# IRIS-FE-01-B-LEDs.net
KiCad netlist of a schematic drawn in Altium Designer
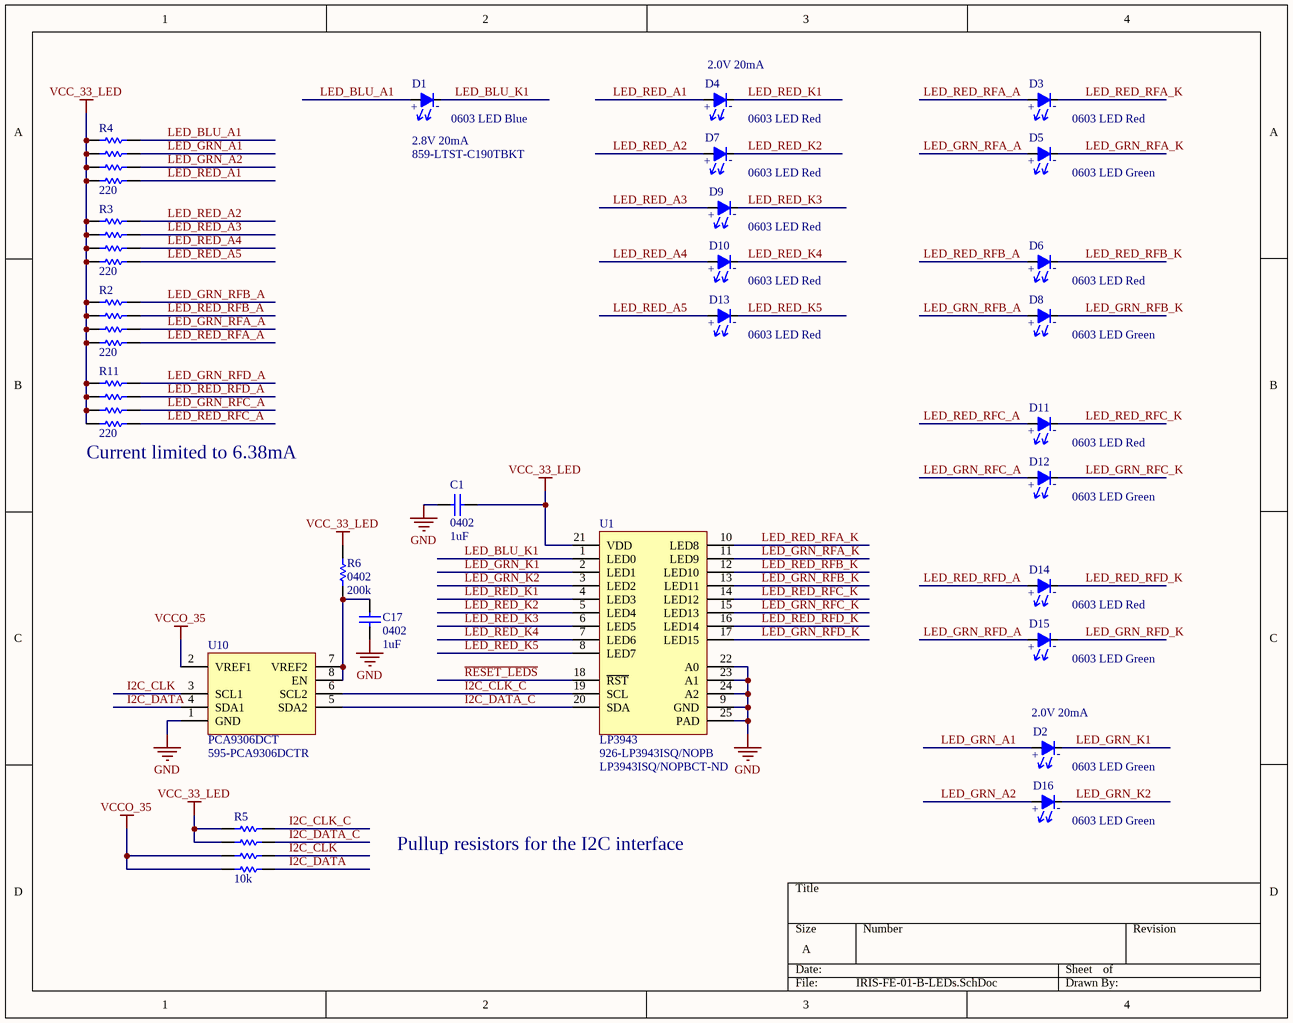
[diagram p0: IRIS-FE-01-B-LEDs.SchDoc]

(export (version "E")
  (design (tool "Eeschema 10.0.6"))
  (components
    (comp (ref "C1")
      (value "0402")
      (footprint "0402_SMT_CAP")
      (description "0402 SMT Capacitor")
      (fields (field (name "ALTIUM_VALUE") "1uF"))
      (libsource (lib "RNG_Parts") (part "Cap_0402"))
    )
    (comp (ref "C17")
      (value "0402")
      (footprint "0402_SMT_CAP")
      (description "0402 SMT Capacitor")
      (fields (field (name "ALTIUM_VALUE") "1uF"))
      (libsource (lib "RNG_Parts") (part "Cap_0402"))
    )
    (comp (ref "D1")
      (value "0603 LED Blue")
      (footprint "0603_SMT_LED_Blue")
      (description "0603 LED with Polar Markings")
      (fields
        (field (name "ALTIUM_VALUE") "2.8V 20mA")
        (field (name "SUPPLIER PART NUMBER 1") "859-LTST-C190TBKT")
      )
      (libsource (lib "Skylark_Master") (part "LED_0603_BLUE"))
    )
    (comp (ref "D2")
      (value "0603 LED Green")
      (footprint "0603_SMT_LED_Green")
      (description "0603 LED with Polar Markings")
      (fields (field (name "ALTIUM_VALUE") "2.0V 20mA"))
      (libsource (lib "Skylark_Master") (part "LED_0603_GREEN"))
    )
    (comp (ref "D3")
      (value "0603 LED Red")
      (footprint "0603_SMT_LED_Red")
      (description "0603 LED with Polar Markings")
      (libsource (lib "Skylark_Master") (part "LED_0603_RED"))
    )
    (comp (ref "D4")
      (value "0603 LED Red")
      (footprint "0603_SMT_LED_Red")
      (description "0603 LED with Polar Markings")
      (fields (field (name "ALTIUM_VALUE") "2.0V 20mA"))
      (libsource (lib "Skylark_Master") (part "LED_0603_RED"))
    )
    (comp (ref "D5")
      (value "0603 LED Green")
      (footprint "0603_SMT_LED_Green")
      (description "0603 LED with Polar Markings")
      (libsource (lib "Skylark_Master") (part "LED_0603_GREEN"))
    )
    (comp (ref "D6")
      (value "0603 LED Red")
      (footprint "0603_SMT_LED_Red")
      (description "0603 LED with Polar Markings")
      (libsource (lib "Skylark_Master") (part "LED_0603_RED"))
    )
    (comp (ref "D7")
      (value "0603 LED Red")
      (footprint "0603_SMT_LED_Red")
      (description "0603 LED with Polar Markings")
      (libsource (lib "Skylark_Master") (part "LED_0603_RED"))
    )
    (comp (ref "D8")
      (value "0603 LED Green")
      (footprint "0603_SMT_LED_Green")
      (description "0603 LED with Polar Markings")
      (libsource (lib "Skylark_Master") (part "LED_0603_GREEN"))
    )
    (comp (ref "D9")
      (value "0603 LED Red")
      (footprint "0603_SMT_LED_Red")
      (description "0603 LED with Polar Markings")
      (libsource (lib "Skylark_Master") (part "LED_0603_RED"))
    )
    (comp (ref "D10")
      (value "0603 LED Red")
      (footprint "0603_SMT_LED_Red")
      (description "0603 LED with Polar Markings")
      (libsource (lib "Skylark_Master") (part "LED_0603_RED"))
    )
    (comp (ref "D11")
      (value "0603 LED Red")
      (footprint "0603_SMT_LED_Red")
      (description "0603 LED with Polar Markings")
      (libsource (lib "Skylark_Master") (part "LED_0603_RED"))
    )
    (comp (ref "D12")
      (value "0603 LED Green")
      (footprint "0603_SMT_LED_Green")
      (description "0603 LED with Polar Markings")
      (libsource (lib "Skylark_Master") (part "LED_0603_GREEN"))
    )
    (comp (ref "D13")
      (value "0603 LED Red")
      (footprint "0603_SMT_LED_Red")
      (description "0603 LED with Polar Markings")
      (libsource (lib "Skylark_Master") (part "LED_0603_RED"))
    )
    (comp (ref "D14")
      (value "0603 LED Red")
      (footprint "0603_SMT_LED_Red")
      (description "0603 LED with Polar Markings")
      (libsource (lib "Skylark_Master") (part "LED_0603_RED"))
    )
    (comp (ref "D15")
      (value "0603 LED Green")
      (footprint "0603_SMT_LED_Green")
      (description "0603 LED with Polar Markings")
      (libsource (lib "Skylark_Master") (part "LED_0603_GREEN"))
    )
    (comp (ref "D16")
      (value "0603 LED Green")
      (footprint "0603_SMT_LED_Green")
      (description "0603 LED with Polar Markings")
      (libsource (lib "Skylark_Master") (part "LED_0603_GREEN"))
    )
    (comp (ref "R2")
      (value "220")
      (footprint "EXB28V")
      (description "0402 SMT Resistor Array")
      (fields (field (name "Comment") "0402 Array"))
      (libsource (lib "Skylark_Master") (part "Res_0402_4xArray"))
    )
    (comp (ref "R3")
      (value "220")
      (footprint "EXB28V")
      (description "0402 SMT Resistor Array")
      (fields (field (name "Comment") "0402 Array"))
      (libsource (lib "Skylark_Master") (part "Res_0402_4xArray"))
    )
    (comp (ref "R4")
      (value "220")
      (footprint "EXB28V")
      (description "0402 SMT Resistor Array")
      (fields (field (name "Comment") "0402 Array"))
      (libsource (lib "Skylark_Master") (part "Res_0402_4xArray"))
    )
    (comp (ref "R5")
      (value "10k")
      (footprint "EXB28V")
      (description "0402 SMT Resistor Array")
      (fields (field (name "Comment") "0402 Array"))
      (libsource (lib "Skylark_Master") (part "Res_0402_4xArray"))
    )
    (comp (ref "R6")
      (value "0402")
      (footprint "0402_SMT_RES")
      (description "0402 SMT Resistor")
      (fields (field (name "ALTIUM_VALUE") "200k"))
      (libsource (lib "Skylark_Master") (part "Res_0402"))
    )
    (comp (ref "R11")
      (value "220")
      (footprint "EXB28V")
      (description "0402 SMT Resistor Array")
      (fields (field (name "Comment") "0402 Array"))
      (libsource (lib "Skylark_Master") (part "Res_0402_4xArray"))
    )
    (comp (ref "U1")
      (value "LP3943")
      (footprint "TI-QFN127P600-8N")
      (description "TI 16-LED Fun Light Driver with I2C")
      (fields
        (field (name "SUPPLIER PART NUMBER 1") "926-LP3943ISQ/NOPB")
        (field (name "SUPPLIER PART NUMBER 2") "LP3943ISQ/NOPBCT-ND")
      )
      (libsource (lib "Skylark_Master") (part "LP3943"))
    )
    (comp (ref "U10")
      (value "PCA9306DCT")
      (footprint "TI-SOP127P600-8N")
      (description "TI I2C Bidirectional Voltage Translator")
      (fields (field (name "SUPPLIER PART NUMBER 1") "595-PCA9306DCTR"))
      (libsource (lib "Skylark_Master") (part "PCA9306DCT"))
    )
  )
  (nets
    (net (code "1") (name "/I2C_CLK") (class "Default")
      (node (ref "R5") (pin "2") (pinfunction "2_2") (pintype "passive"))
      (node (ref "U10") (pin "3") (pinfunction "SCL1_3") (pintype "passive"))
    )
    (net (code "2") (name "/I2C_CLK_C") (class "Default")
      (node (ref "R5") (pin "4") (pinfunction "4_4") (pintype "passive"))
      (node (ref "U1") (pin "19") (pinfunction "SCL_19") (pintype "passive"))
      (node (ref "U10") (pin "6") (pinfunction "SCL2_6") (pintype "passive"))
    )
    (net (code "3") (name "/I2C_DATA") (class "Default")
      (node (ref "R5") (pin "1") (pinfunction "1_1") (pintype "passive"))
      (node (ref "U10") (pin "4") (pinfunction "SDA1_4") (pintype "passive"))
    )
    (net (code "4") (name "/I2C_DATA_C") (class "Default")
      (node (ref "R5") (pin "3") (pinfunction "3_3") (pintype "passive"))
      (node (ref "U1") (pin "20") (pinfunction "SDA_20") (pintype "passive"))
      (node (ref "U10") (pin "5") (pinfunction "SDA2_5") (pintype "passive"))
    )
    (net (code "5") (name "/LED_BLU_A1") (class "Default")
      (node (ref "D1") (pin "1") (pinfunction "P_1") (pintype "passive"))
      (node (ref "R4") (pin "8") (pinfunction "8_8") (pintype "passive"))
    )
    (net (code "6") (name "/LED_BLU_K1") (class "Default")
      (node (ref "D1") (pin "2") (pinfunction "N_2") (pintype "passive"))
      (node (ref "U1") (pin "1") (pinfunction "LED0_1") (pintype "passive"))
    )
    (net (code "7") (name "/LED_GRN_A1") (class "Default")
      (node (ref "D2") (pin "1") (pinfunction "P_1") (pintype "passive"))
      (node (ref "R4") (pin "7") (pinfunction "7_7") (pintype "passive"))
    )
    (net (code "8") (name "/LED_GRN_A2") (class "Default")
      (node (ref "D16") (pin "1") (pinfunction "P_1") (pintype "passive"))
      (node (ref "R4") (pin "6") (pinfunction "6_6") (pintype "passive"))
    )
    (net (code "9") (name "/LED_GRN_K1") (class "Default")
      (node (ref "D2") (pin "2") (pinfunction "N_2") (pintype "passive"))
      (node (ref "U1") (pin "2") (pinfunction "LED1_2") (pintype "passive"))
    )
    (net (code "10") (name "/LED_GRN_K2") (class "Default")
      (node (ref "D16") (pin "2") (pinfunction "N_2") (pintype "passive"))
      (node (ref "U1") (pin "3") (pinfunction "LED2_3") (pintype "passive"))
    )
    (net (code "11") (name "/LED_GRN_RFA_A") (class "Default")
      (node (ref "D5") (pin "1") (pinfunction "P_1") (pintype "passive"))
      (node (ref "R2") (pin "6") (pinfunction "6_6") (pintype "passive"))
    )
    (net (code "12") (name "/LED_GRN_RFA_K") (class "Default")
      (node (ref "D5") (pin "2") (pinfunction "N_2") (pintype "passive"))
      (node (ref "U1") (pin "11") (pinfunction "LED9_11") (pintype "passive"))
    )
    (net (code "13") (name "/LED_GRN_RFB_A") (class "Default")
      (node (ref "D8") (pin "1") (pinfunction "P_1") (pintype "passive"))
      (node (ref "R2") (pin "8") (pinfunction "8_8") (pintype "passive"))
    )
    (net (code "14") (name "/LED_GRN_RFB_K") (class "Default")
      (node (ref "D8") (pin "2") (pinfunction "N_2") (pintype "passive"))
      (node (ref "U1") (pin "13") (pinfunction "LED11_13") (pintype "passive"))
    )
    (net (code "15") (name "/LED_GRN_RFC_A") (class "Default")
      (node (ref "D12") (pin "1") (pinfunction "P_1") (pintype "passive"))
      (node (ref "R11") (pin "6") (pinfunction "6_6") (pintype "passive"))
    )
    (net (code "16") (name "/LED_GRN_RFC_K") (class "Default")
      (node (ref "D12") (pin "2") (pinfunction "N_2") (pintype "passive"))
      (node (ref "U1") (pin "15") (pinfunction "LED13_15") (pintype "passive"))
    )
    (net (code "17") (name "/LED_GRN_RFD_A") (class "Default")
      (node (ref "D15") (pin "1") (pinfunction "P_1") (pintype "passive"))
      (node (ref "R11") (pin "8") (pinfunction "8_8") (pintype "passive"))
    )
    (net (code "18") (name "/LED_GRN_RFD_K") (class "Default")
      (node (ref "D15") (pin "2") (pinfunction "N_2") (pintype "passive"))
      (node (ref "U1") (pin "17") (pinfunction "LED15_17") (pintype "passive"))
    )
    (net (code "19") (name "/LED_RED_A1") (class "Default")
      (node (ref "D4") (pin "1") (pinfunction "P_1") (pintype "passive"))
      (node (ref "R4") (pin "5") (pinfunction "5_5") (pintype "passive"))
    )
    (net (code "20") (name "/LED_RED_A2") (class "Default")
      (node (ref "D7") (pin "1") (pinfunction "P_1") (pintype "passive"))
      (node (ref "R3") (pin "8") (pinfunction "8_8") (pintype "passive"))
    )
    (net (code "21") (name "/LED_RED_A3") (class "Default")
      (node (ref "D9") (pin "1") (pinfunction "P_1") (pintype "passive"))
      (node (ref "R3") (pin "7") (pinfunction "7_7") (pintype "passive"))
    )
    (net (code "22") (name "/LED_RED_A4") (class "Default")
      (node (ref "D10") (pin "1") (pinfunction "P_1") (pintype "passive"))
      (node (ref "R3") (pin "6") (pinfunction "6_6") (pintype "passive"))
    )
    (net (code "23") (name "/LED_RED_A5") (class "Default")
      (node (ref "D13") (pin "1") (pinfunction "P_1") (pintype "passive"))
      (node (ref "R3") (pin "5") (pinfunction "5_5") (pintype "passive"))
    )
    (net (code "24") (name "/LED_RED_K1") (class "Default")
      (node (ref "D4") (pin "2") (pinfunction "N_2") (pintype "passive"))
      (node (ref "U1") (pin "4") (pinfunction "LED3_4") (pintype "passive"))
    )
    (net (code "25") (name "/LED_RED_K2") (class "Default")
      (node (ref "D7") (pin "2") (pinfunction "N_2") (pintype "passive"))
      (node (ref "U1") (pin "5") (pinfunction "LED4_5") (pintype "passive"))
    )
    (net (code "26") (name "/LED_RED_K3") (class "Default")
      (node (ref "D9") (pin "2") (pinfunction "N_2") (pintype "passive"))
      (node (ref "U1") (pin "6") (pinfunction "LED5_6") (pintype "passive"))
    )
    (net (code "27") (name "/LED_RED_K4") (class "Default")
      (node (ref "D10") (pin "2") (pinfunction "N_2") (pintype "passive"))
      (node (ref "U1") (pin "7") (pinfunction "LED6_7") (pintype "passive"))
    )
    (net (code "28") (name "/LED_RED_K5") (class "Default")
      (node (ref "D13") (pin "2") (pinfunction "N_2") (pintype "passive"))
      (node (ref "U1") (pin "8") (pinfunction "LED7_8") (pintype "passive"))
    )
    (net (code "29") (name "/LED_RED_RFA_A") (class "Default")
      (node (ref "D3") (pin "1") (pinfunction "P_1") (pintype "passive"))
      (node (ref "R2") (pin "5") (pinfunction "5_5") (pintype "passive"))
    )
    (net (code "30") (name "/LED_RED_RFA_K") (class "Default")
      (node (ref "D3") (pin "2") (pinfunction "N_2") (pintype "passive"))
      (node (ref "U1") (pin "10") (pinfunction "LED8_10") (pintype "passive"))
    )
    (net (code "31") (name "/LED_RED_RFB_A") (class "Default")
      (node (ref "D6") (pin "1") (pinfunction "P_1") (pintype "passive"))
      (node (ref "R2") (pin "7") (pinfunction "7_7") (pintype "passive"))
    )
    (net (code "32") (name "/LED_RED_RFB_K") (class "Default")
      (node (ref "D6") (pin "2") (pinfunction "N_2") (pintype "passive"))
      (node (ref "U1") (pin "12") (pinfunction "LED10_12") (pintype "passive"))
    )
    (net (code "33") (name "/LED_RED_RFC_A") (class "Default")
      (node (ref "D11") (pin "1") (pinfunction "P_1") (pintype "passive"))
      (node (ref "R11") (pin "5") (pinfunction "5_5") (pintype "passive"))
    )
    (net (code "34") (name "/LED_RED_RFC_K") (class "Default")
      (node (ref "D11") (pin "2") (pinfunction "N_2") (pintype "passive"))
      (node (ref "U1") (pin "14") (pinfunction "LED12_14") (pintype "passive"))
    )
    (net (code "35") (name "/LED_RED_RFD_A") (class "Default")
      (node (ref "D14") (pin "1") (pinfunction "P_1") (pintype "passive"))
      (node (ref "R11") (pin "7") (pinfunction "7_7") (pintype "passive"))
    )
    (net (code "36") (name "/LED_RED_RFD_K") (class "Default")
      (node (ref "D14") (pin "2") (pinfunction "N_2") (pintype "passive"))
      (node (ref "U1") (pin "16") (pinfunction "LED14_16") (pintype "passive"))
    )
    (net (code "37") (name "/RESET_LEDS") (class "Default")
      (node (ref "U1") (pin "18") (pinfunction "RST_18") (pintype "passive"))
    )
    (net (code "38") (name "GND") (class "Default")
      (node (ref "C1") (pin "2") (pinfunction "2_2") (pintype "passive"))
      (node (ref "C17") (pin "1") (pinfunction "1_1") (pintype "passive"))
      (node (ref "U1") (pin "22") (pinfunction "A0_22") (pintype "passive"))
      (node (ref "U1") (pin "23") (pinfunction "A1_23") (pintype "passive"))
      (node (ref "U1") (pin "24") (pinfunction "A2_24") (pintype "passive"))
      (node (ref "U1") (pin "25") (pinfunction "PAD_25") (pintype "passive"))
      (node (ref "U1") (pin "9") (pinfunction "GND_9") (pintype "passive"))
      (node (ref "U10") (pin "1") (pinfunction "GND_1") (pintype "passive"))
    )
    (net (code "39") (name "Net-(U10-EN)") (class "Default")
      (node (ref "C17") (pin "2") (pinfunction "2_2") (pintype "passive"))
      (node (ref "R6") (pin "1") (pinfunction "1_1") (pintype "passive"))
      (node (ref "U10") (pin "7") (pinfunction "VREF2_7") (pintype "passive"))
      (node (ref "U10") (pin "8") (pinfunction "EN_8") (pintype "passive"))
    )
    (net (code "40") (name "VCCO_35") (class "Default")
      (node (ref "R5") (pin "7") (pinfunction "7_7") (pintype "passive"))
      (node (ref "R5") (pin "8") (pinfunction "8_8") (pintype "passive"))
      (node (ref "U10") (pin "2") (pinfunction "VREF1_2") (pintype "passive"))
    )
    (net (code "41") (name "VCC_33_LED") (class "Default")
      (node (ref "C1") (pin "1") (pinfunction "1_1") (pintype "passive"))
      (node (ref "R11") (pin "1") (pinfunction "1_1") (pintype "passive"))
      (node (ref "R11") (pin "2") (pinfunction "2_2") (pintype "passive"))
      (node (ref "R11") (pin "3") (pinfunction "3_3") (pintype "passive"))
      (node (ref "R11") (pin "4") (pinfunction "4_4") (pintype "passive"))
      (node (ref "R2") (pin "1") (pinfunction "1_1") (pintype "passive"))
      (node (ref "R2") (pin "2") (pinfunction "2_2") (pintype "passive"))
      (node (ref "R2") (pin "3") (pinfunction "3_3") (pintype "passive"))
      (node (ref "R2") (pin "4") (pinfunction "4_4") (pintype "passive"))
      (node (ref "R3") (pin "1") (pinfunction "1_1") (pintype "passive"))
      (node (ref "R3") (pin "2") (pinfunction "2_2") (pintype "passive"))
      (node (ref "R3") (pin "3") (pinfunction "3_3") (pintype "passive"))
      (node (ref "R3") (pin "4") (pinfunction "4_4") (pintype "passive"))
      (node (ref "R4") (pin "1") (pinfunction "1_1") (pintype "passive"))
      (node (ref "R4") (pin "2") (pinfunction "2_2") (pintype "passive"))
      (node (ref "R4") (pin "3") (pinfunction "3_3") (pintype "passive"))
      (node (ref "R4") (pin "4") (pinfunction "4_4") (pintype "passive"))
      (node (ref "R5") (pin "5") (pinfunction "5_5") (pintype "passive"))
      (node (ref "R5") (pin "6") (pinfunction "6_6") (pintype "passive"))
      (node (ref "R6") (pin "2") (pinfunction "2_2") (pintype "passive"))
      (node (ref "U1") (pin "21") (pinfunction "VDD_21") (pintype "passive"))
    )
  )
)
